# PROC099B_DUT_Reference.net
KiCad netlist of a schematic drawn in Altium Designer
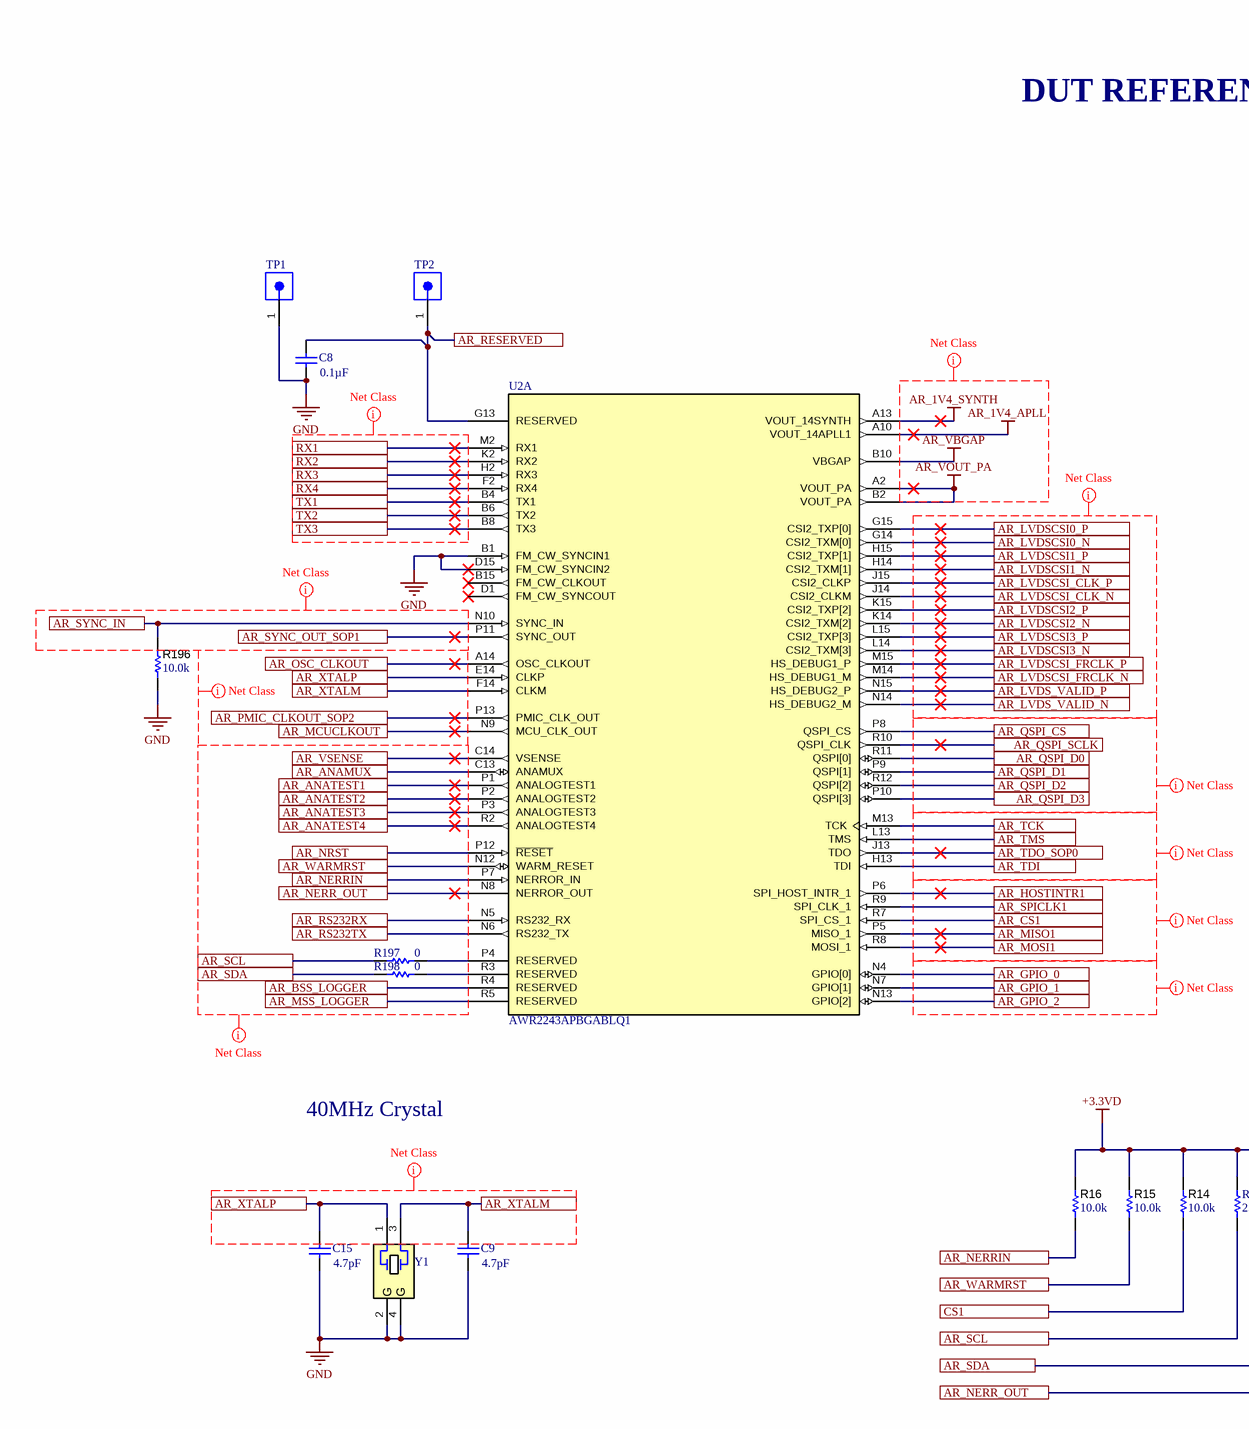
[diagram p0: PROC099B_DUT_Reference.SchDoc, left]
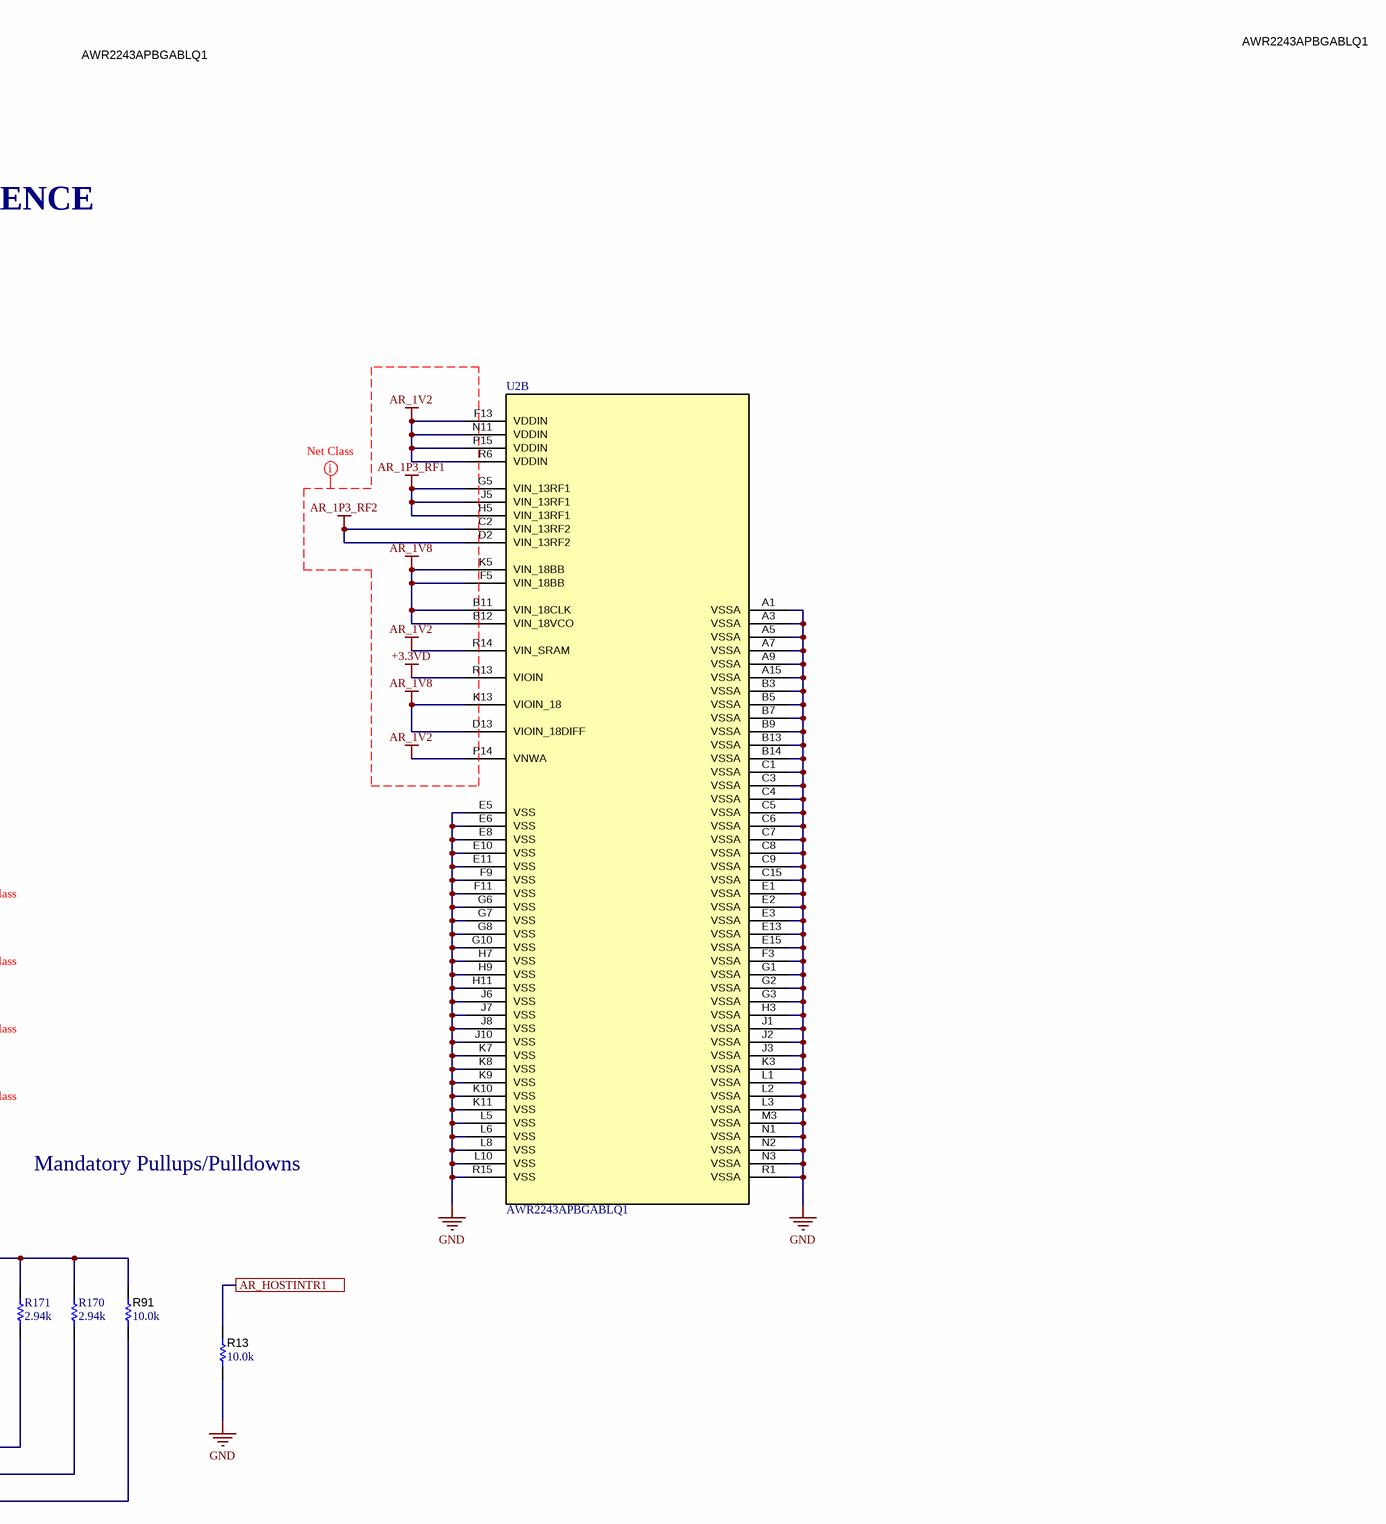
[diagram p1: PROC099B_DUT_Reference.SchDoc, right]

(export (version "E")
  (design (tool "Eeschema 10.0.6"))
  (components
    (comp (ref "C8")
      (value "C0603X7S1A104K030BC")
      (footprint "0201_033")
      (description "CAP, CERM, 0.1 µF, 10 V,+/- 10%, X7S, 0201")
      (fields (field (name "MANUFACTURER") "TDK") (field (name "VALUEDISPLAYED") "0.1µF"))
      (libsource (lib "Altium Vault - TI") (part "Capacitor"))
    )
    (comp (ref "C9")
      (value "GJM1555C1H4R7BB01D")
      (footprint "0402")
      (description "CAP, CERM, 4.7 pF, 50 V, +/- 2%, C0G/NP0, 0402")
      (fields
        (field (name "MANUFACTURER") "MuRata")
        (field (name "VALUEDISPLAYED") "4.7pF")
        (field (name "PUBLISHER") "Texas Instruments")
      )
      (libsource (lib "Altium Vault - TI") (part "CMP-0006367-2"))
    )
    (comp (ref "C15")
      (value "GJM1555C1H4R7BB01D")
      (footprint "0402")
      (description "CAP, CERM, 4.7 pF, 50 V, +/- 2%, C0G/NP0, 0402")
      (fields
        (field (name "MANUFACTURER") "MuRata")
        (field (name "VALUEDISPLAYED") "4.7pF")
        (field (name "PUBLISHER") "Texas Instruments")
      )
      (libsource (lib "Altium Vault - TI") (part "CMP-0006367-2"))
    )
    (comp (ref "R13")
      (value "CRCW040210K0FKED")
      (footprint "0402L")
      (description "RES, 10.0 k, 1%, 0.063 W, AEC-Q200 Grade 0, 0402")
      (fields (field (name "MANUFACTURER") "Vishay-Dale") (field (name "VALUEDISPLAYED") "10.0k"))
      (libsource (lib "Altium Vault - TI") (part "Resistor"))
    )
    (comp (ref "R14")
      (value "CRCW040210K0FKED")
      (footprint "0402L")
      (description "RES, 10.0 k, 1%, 0.063 W, AEC-Q200 Grade 0, 0402")
      (fields (field (name "MANUFACTURER") "Vishay-Dale") (field (name "VALUEDISPLAYED") "10.0k"))
      (libsource (lib "Altium Vault - TI") (part "Resistor"))
    )
    (comp (ref "R15")
      (value "CRCW040210K0FKED")
      (footprint "0402L")
      (description "RES, 10.0 k, 1%, 0.063 W, AEC-Q200 Grade 0, 0402")
      (fields (field (name "MANUFACTURER") "Vishay-Dale") (field (name "VALUEDISPLAYED") "10.0k"))
      (libsource (lib "Altium Vault - TI") (part "Resistor"))
    )
    (comp (ref "R16")
      (value "CRCW040210K0FKED")
      (footprint "0402L")
      (description "RES, 10.0 k, 1%, 0.063 W, AEC-Q200 Grade 0, 0402")
      (fields (field (name "MANUFACTURER") "Vishay-Dale") (field (name "VALUEDISPLAYED") "10.0k"))
      (libsource (lib "Altium Vault - TI") (part "Resistor"))
    )
    (comp (ref "R91")
      (value "CRCW040210K0FKED")
      (footprint "0402L")
      (description "RES, 10.0 k, 1%, 0.063 W, AEC-Q200 Grade 0, 0402")
      (fields (field (name "MANUFACTURER") "Vishay-Dale") (field (name "VALUEDISPLAYED") "10.0k"))
      (libsource (lib "Altium Vault - TI") (part "Resistor"))
    )
    (comp (ref "R170")
      (value "CRCW04022K94FKED")
      (footprint "0402")
      (description "RES, 2.94 k, 1%, 0.063 W, AEC-Q200 Grade 0, 0402")
      (fields (field (name "MANUFACTURER") "Vishay-Dale") (field (name "VALUEDISPLAYED") "2.94k"))
      (libsource (lib "Altium Vault - TI") (part "Resistor"))
    )
    (comp (ref "R171")
      (value "CRCW04022K94FKED")
      (footprint "0402")
      (description "RES, 2.94 k, 1%, 0.063 W, AEC-Q200 Grade 0, 0402")
      (fields (field (name "MANUFACTURER") "Vishay-Dale") (field (name "VALUEDISPLAYED") "2.94k"))
      (libsource (lib "Altium Vault - TI") (part "Resistor"))
    )
    (comp (ref "R196")
      (value "CRCW040210K0FKED")
      (footprint "0402L")
      (description "RES, 10.0 k, 1%, 0.063 W, AEC-Q200 Grade 0, 0402")
      (fields (field (name "MANUFACTURER") "Vishay-Dale") (field (name "VALUEDISPLAYED") "10.0k"))
      (libsource (lib "Altium Vault - TI") (part "CMP-0025958-3"))
    )
    (comp (ref "R197")
      (value "CRCW02010000Z0ED")
      (footprint "0201")
      (description "RES, 0, 5%, 0.05 W, 0201")
      (fields (field (name "MANUFACTURER") "Vishay-Dale") (field (name "VALUEDISPLAYED") "0"))
      (libsource (lib "Altium Vault - TI") (part "Resistor"))
    )
    (comp (ref "R198")
      (value "CRCW02010000Z0ED")
      (footprint "0201")
      (description "RES, 0, 5%, 0.05 W, 0201")
      (fields (field (name "MANUFACTURER") "Vishay-Dale") (field (name "VALUEDISPLAYED") "0"))
      (libsource (lib "Altium Vault - TI") (part "Resistor"))
    )
    (comp (ref "TP1")
      (value "TSW-101-17-T-S")
      (footprint "Samtec_TSW-101-17-T-S")
      (description "Header, 100mil, 1x1, Tin, TH")
      (fields (field (name "MANUFACTURER") "Samtec") (field (name "PUBLISHER") "Texas Instruments"))
      (libsource (lib "Altium Vault - TI") (part "Header_1x1"))
    )
    (comp (ref "TP2")
      (value "TSW-101-17-T-S")
      (footprint "Samtec_TSW-101-17-T-S")
      (description "Header, 100mil, 1x1, Tin, TH")
      (fields (field (name "MANUFACTURER") "Samtec") (field (name "PUBLISHER") "Texas Instruments"))
      (libsource (lib "Altium Vault - TI") (part "Header_1x1"))
    )
    (comp (ref "U2")
      (value "AWR2243APBGABLQ1")
      (footprint "ABL0161A")
      (description "Single Chip 77 and 79 GHz FMCW Transceiver, ABL0161A (FCBGA-161)")
      (fields
        (field (name "MANUFACTURER") "Texas Instruments")
        (field (name "PARTNUMBER") "AWR2243APBGABLQ1")
      )
      (libsource (lib "Altium Vault - TI") (part "CMP-0081285-1"))
    )
    (comp (ref "Y1")
      (value "CX3225SA40000D0PTWCC")
      (footprint "Kyocera_CX3225SA")
      (description "Crystal, 40 MHz, 8pF, SMD")
      (fields (field (name "MANUFACTURER") "Kyocera"))
      (libsource (lib "Altium Vault - TI") (part "XTAL_4P_13_24OPEN"))
    )
  )
  (nets
    (net (code "1") (name "+3.3VD") (class "Default")
      (node (ref "R14") (pin "2") (pinfunction "2_2") (pintype "passive"))
      (node (ref "R15") (pin "2") (pinfunction "2_2") (pintype "passive"))
      (node (ref "R16") (pin "2") (pinfunction "2_2") (pintype "passive"))
      (node (ref "R170") (pin "2") (pinfunction "2_2") (pintype "passive"))
      (node (ref "R171") (pin "2") (pinfunction "2_2") (pintype "passive"))
      (node (ref "R91") (pin "2") (pinfunction "2_2") (pintype "passive"))
      (node (ref "U2") (pin "R13") (pinfunction "VIOIN_R13") (pintype "power_in"))
    )
    (net (code "2") (name "/AR_ANAMUX") (class "Default")
      (node (ref "U2") (pin "C13") (pinfunction "ANAMUX_C13") (pintype "bidirectional"))
    )
    (net (code "3") (name "/AR_ANATEST1") (class "Default")
      (node (ref "U2") (pin "P1") (pinfunction "ANALOGTEST1_P1") (pintype "output"))
    )
    (net (code "4") (name "/AR_ANATEST2") (class "Default")
      (node (ref "U2") (pin "P2") (pinfunction "ANALOGTEST2_P2") (pintype "output"))
    )
    (net (code "5") (name "/AR_ANATEST3") (class "Default")
      (node (ref "U2") (pin "P3") (pinfunction "ANALOGTEST3_P3") (pintype "output"))
    )
    (net (code "6") (name "/AR_ANATEST4") (class "Default")
      (node (ref "U2") (pin "R2") (pinfunction "ANALOGTEST4_R2") (pintype "output"))
    )
    (net (code "7") (name "/AR_BSS_LOGGER") (class "Default")
      (node (ref "U2") (pin "R4") (pinfunction "RESERVED_R4") (pintype "passive"))
    )
    (net (code "8") (name "/AR_CS1") (class "Default")
      (node (ref "U2") (pin "R7") (pinfunction "SPI_CS_1_R7") (pintype "input"))
    )
    (net (code "9") (name "/AR_GPIO_0") (class "Default")
      (node (ref "U2") (pin "N4") (pinfunction "GPIO[0]_N4") (pintype "bidirectional"))
    )
    (net (code "10") (name "/AR_GPIO_1") (class "Default")
      (node (ref "U2") (pin "N7") (pinfunction "GPIO[1]_N7") (pintype "bidirectional"))
    )
    (net (code "11") (name "/AR_GPIO_2") (class "Default")
      (node (ref "U2") (pin "N13") (pinfunction "GPIO[2]_N13") (pintype "bidirectional"))
    )
    (net (code "12") (name "/AR_HOSTINTR1") (class "Default")
      (node (ref "R13") (pin "2") (pinfunction "2_2") (pintype "passive"))
      (node (ref "U2") (pin "P6") (pinfunction "SPI_HOST_INTR_1_P6") (pintype "output"))
    )
    (net (code "13") (name "/AR_LVDSCSI0_N") (class "Default")
      (node (ref "U2") (pin "G14") (pinfunction "CSI2_TXM[0]_G14") (pintype "output"))
    )
    (net (code "14") (name "/AR_LVDSCSI0_P") (class "Default")
      (node (ref "U2") (pin "G15") (pinfunction "CSI2_TXP[0]_G15") (pintype "output"))
    )
    (net (code "15") (name "/AR_LVDSCSI1_N") (class "Default")
      (node (ref "U2") (pin "H14") (pinfunction "CSI2_TXM[1]_H14") (pintype "output"))
    )
    (net (code "16") (name "/AR_LVDSCSI1_P") (class "Default")
      (node (ref "U2") (pin "H15") (pinfunction "CSI2_TXP[1]_H15") (pintype "output"))
    )
    (net (code "17") (name "/AR_LVDSCSI2_N") (class "Default")
      (node (ref "U2") (pin "K14") (pinfunction "CSI2_TXM[2]_K14") (pintype "output"))
    )
    (net (code "18") (name "/AR_LVDSCSI2_P") (class "Default")
      (node (ref "U2") (pin "K15") (pinfunction "CSI2_TXP[2]_K15") (pintype "output"))
    )
    (net (code "19") (name "/AR_LVDSCSI3_N") (class "Default")
      (node (ref "U2") (pin "L14") (pinfunction "CSI2_TXM[3]_L14") (pintype "output"))
    )
    (net (code "20") (name "/AR_LVDSCSI3_P") (class "Default")
      (node (ref "U2") (pin "L15") (pinfunction "CSI2_TXP[3]_L15") (pintype "output"))
    )
    (net (code "21") (name "/AR_LVDSCSI_CLK_N") (class "Default")
      (node (ref "U2") (pin "J14") (pinfunction "CSI2_CLKM_J14") (pintype "output"))
    )
    (net (code "22") (name "/AR_LVDSCSI_CLK_P") (class "Default")
      (node (ref "U2") (pin "J15") (pinfunction "CSI2_CLKP_J15") (pintype "output"))
    )
    (net (code "23") (name "/AR_LVDSCSI_FRCLK_N") (class "Default")
      (node (ref "U2") (pin "M14") (pinfunction "HS_DEBUG1_M_M14") (pintype "output"))
    )
    (net (code "24") (name "/AR_LVDSCSI_FRCLK_P") (class "Default")
      (node (ref "U2") (pin "M15") (pinfunction "HS_DEBUG1_P_M15") (pintype "output"))
    )
    (net (code "25") (name "/AR_LVDS_VALID_N") (class "Default")
      (node (ref "U2") (pin "N14") (pinfunction "HS_DEBUG2_M_N14") (pintype "output"))
    )
    (net (code "26") (name "/AR_LVDS_VALID_P") (class "Default")
      (node (ref "U2") (pin "N15") (pinfunction "HS_DEBUG2_P_N15") (pintype "output"))
    )
    (net (code "27") (name "/AR_MCUCLKOUT") (class "Default")
      (node (ref "U2") (pin "N9") (pinfunction "MCU_CLK_OUT_N9") (pintype "output"))
    )
    (net (code "28") (name "/AR_MISO1") (class "Default")
      (node (ref "U2") (pin "P5") (pinfunction "MISO_1_P5") (pintype "output"))
    )
    (net (code "29") (name "/AR_MOSI1") (class "Default")
      (node (ref "U2") (pin "R8") (pinfunction "MOSI_1_R8") (pintype "input"))
    )
    (net (code "30") (name "/AR_MSS_LOGGER") (class "Default")
      (node (ref "U2") (pin "R5") (pinfunction "RESERVED_R5") (pintype "passive"))
    )
    (net (code "31") (name "/AR_NERRIN") (class "Default")
      (node (ref "R16") (pin "1") (pinfunction "1_1") (pintype "passive"))
      (node (ref "U2") (pin "P7") (pinfunction "NERROR_IN_P7") (pintype "input"))
    )
    (net (code "32") (name "/AR_NERR_OUT") (class "Default")
      (node (ref "R91") (pin "1") (pinfunction "1_1") (pintype "passive"))
      (node (ref "U2") (pin "N8") (pinfunction "NERROR_OUT_N8") (pintype "open_collector"))
    )
    (net (code "33") (name "/AR_NRST") (class "Default")
      (node (ref "U2") (pin "P12") (pinfunction "RESET_P12") (pintype "input"))
    )
    (net (code "34") (name "/AR_OSC_CLKOUT") (class "Default")
      (node (ref "U2") (pin "A14") (pinfunction "OSC_CLKOUT_A14") (pintype "output"))
    )
    (net (code "35") (name "/AR_PMIC_CLKOUT_SOP2") (class "Default")
      (node (ref "U2") (pin "P13") (pinfunction "PMIC_CLK_OUT_P13") (pintype "output"))
    )
    (net (code "36") (name "/AR_QSPI_CS") (class "Default")
      (node (ref "U2") (pin "P8") (pinfunction "QSPI_CS_P8") (pintype "output"))
    )
    (net (code "37") (name "/AR_QSPI_D0") (class "Default")
      (node (ref "U2") (pin "R11") (pinfunction "QSPI[0]_R11") (pintype "bidirectional"))
    )
    (net (code "38") (name "/AR_QSPI_D1") (class "Default")
      (node (ref "U2") (pin "P9") (pinfunction "QSPI[1]_P9") (pintype "bidirectional"))
    )
    (net (code "39") (name "/AR_QSPI_D2") (class "Default")
      (node (ref "U2") (pin "R12") (pinfunction "QSPI[2]_R12") (pintype "bidirectional"))
    )
    (net (code "40") (name "/AR_QSPI_D3") (class "Default")
      (node (ref "U2") (pin "P10") (pinfunction "QSPI[3]_P10") (pintype "bidirectional"))
    )
    (net (code "41") (name "/AR_QSPI_SCLK") (class "Default")
      (node (ref "U2") (pin "R10") (pinfunction "QSPI_CLK_R10") (pintype "output"))
    )
    (net (code "42") (name "/AR_RESERVED") (class "Default")
      (node (ref "C8") (pin "1") (pinfunction "1_1") (pintype "passive"))
      (node (ref "TP2") (pin "1") (pinfunction "1_1") (pintype "passive"))
      (node (ref "U2") (pin "G13") (pinfunction "RESERVED_G13") (pintype "power_in"))
    )
    (net (code "43") (name "/AR_RS232RX") (class "Default")
      (node (ref "U2") (pin "N5") (pinfunction "RS232_RX_N5") (pintype "input"))
    )
    (net (code "44") (name "/AR_RS232TX") (class "Default")
      (node (ref "U2") (pin "N6") (pinfunction "RS232_TX_N6") (pintype "output"))
    )
    (net (code "45") (name "/AR_SCL") (class "Default")
      (node (ref "R171") (pin "1") (pinfunction "1_1") (pintype "passive"))
      (node (ref "R197") (pin "1") (pinfunction "1_1") (pintype "passive"))
    )
    (net (code "46") (name "/AR_SDA") (class "Default")
      (node (ref "R170") (pin "1") (pinfunction "1_1") (pintype "passive"))
      (node (ref "R198") (pin "1") (pinfunction "1_1") (pintype "passive"))
    )
    (net (code "47") (name "/AR_SPICLK1") (class "Default")
      (node (ref "U2") (pin "R9") (pinfunction "SPI_CLK_1_R9") (pintype "input"))
    )
    (net (code "48") (name "/AR_SYNC_IN") (class "Default")
      (node (ref "R196") (pin "2") (pinfunction "2_2") (pintype "passive"))
      (node (ref "U2") (pin "N10") (pinfunction "SYNC_IN_N10") (pintype "input"))
    )
    (net (code "49") (name "/AR_SYNC_OUT_SOP1") (class "Default")
      (node (ref "U2") (pin "P11") (pinfunction "SYNC_OUT_P11") (pintype "output"))
    )
    (net (code "50") (name "/AR_TCK") (class "Default")
      (node (ref "U2") (pin "M13") (pinfunction "TCK_M13") (pintype "input"))
    )
    (net (code "51") (name "/AR_TDI") (class "Default")
      (node (ref "U2") (pin "H13") (pinfunction "TDI_H13") (pintype "input"))
    )
    (net (code "52") (name "/AR_TDO_SOP0") (class "Default")
      (node (ref "U2") (pin "J13") (pinfunction "TDO_J13") (pintype "output"))
    )
    (net (code "53") (name "/AR_TMS") (class "Default")
      (node (ref "U2") (pin "L13") (pinfunction "TMS_L13") (pintype "input"))
    )
    (net (code "54") (name "/AR_VSENSE") (class "Default")
      (node (ref "U2") (pin "C14") (pinfunction "VSENSE_C14") (pintype "output"))
    )
    (net (code "55") (name "/AR_WARMRST") (class "Default")
      (node (ref "R15") (pin "1") (pinfunction "1_1") (pintype "passive"))
      (node (ref "U2") (pin "N12") (pinfunction "WARM_RESET_N12") (pintype "bidirectional"))
    )
    (net (code "56") (name "/AR_XTALM") (class "Default")
      (node (ref "C9") (pin "1") (pinfunction "1_1") (pintype "passive"))
      (node (ref "U2") (pin "F14") (pinfunction "CLKM_F14") (pintype "input"))
      (node (ref "Y1") (pin "3") (pinfunction "3_3") (pintype "passive"))
    )
    (net (code "57") (name "/AR_XTALP") (class "Default")
      (node (ref "C15") (pin "2") (pinfunction "2_2") (pintype "passive"))
      (node (ref "U2") (pin "E14") (pinfunction "CLKP_E14") (pintype "input"))
      (node (ref "Y1") (pin "1") (pinfunction "1_1") (pintype "passive"))
    )
    (net (code "58") (name "/CS1") (class "Default")
      (node (ref "R14") (pin "1") (pinfunction "1_1") (pintype "passive"))
    )
    (net (code "59") (name "/RX1") (class "Default")
      (node (ref "U2") (pin "M2") (pinfunction "RX1_M2") (pintype "input"))
    )
    (net (code "60") (name "/RX2") (class "Default")
      (node (ref "U2") (pin "K2") (pinfunction "RX2_K2") (pintype "input"))
    )
    (net (code "61") (name "/RX3") (class "Default")
      (node (ref "U2") (pin "H2") (pinfunction "RX3_H2") (pintype "input"))
    )
    (net (code "62") (name "/RX4") (class "Default")
      (node (ref "U2") (pin "F2") (pinfunction "RX4_F2") (pintype "input"))
    )
    (net (code "63") (name "/TX1") (class "Default")
      (node (ref "U2") (pin "B4") (pinfunction "TX1_B4") (pintype "output"))
    )
    (net (code "64") (name "/TX2") (class "Default")
      (node (ref "U2") (pin "B6") (pinfunction "TX2_B6") (pintype "output"))
    )
    (net (code "65") (name "/TX3") (class "Default")
      (node (ref "U2") (pin "B8") (pinfunction "TX3_B8") (pintype "output"))
    )
    (net (code "66") (name "AR_1P3_RF1") (class "Default")
      (node (ref "U2") (pin "G5") (pinfunction "VIN_13RF1_G5") (pintype "power_in"))
      (node (ref "U2") (pin "H5") (pinfunction "VIN_13RF1_H5") (pintype "power_in"))
      (node (ref "U2") (pin "J5") (pinfunction "VIN_13RF1_J5") (pintype "power_in"))
    )
    (net (code "67") (name "AR_1P3_RF2") (class "Default")
      (node (ref "U2") (pin "C2") (pinfunction "VIN_13RF2_C2") (pintype "power_in"))
      (node (ref "U2") (pin "D2") (pinfunction "VIN_13RF2_D2") (pintype "power_in"))
    )
    (net (code "68") (name "AR_1V2") (class "Default")
      (node (ref "U2") (pin "F13") (pinfunction "VDDIN_F13") (pintype "power_in"))
      (node (ref "U2") (pin "N11") (pinfunction "VDDIN_N11") (pintype "power_in"))
      (node (ref "U2") (pin "P14") (pinfunction "VNWA_P14") (pintype "power_in"))
      (node (ref "U2") (pin "P15") (pinfunction "VDDIN_P15") (pintype "power_in"))
      (node (ref "U2") (pin "R14") (pinfunction "VIN_SRAM_R14") (pintype "power_in"))
      (node (ref "U2") (pin "R6") (pinfunction "VDDIN_R6") (pintype "power_in"))
    )
    (net (code "69") (name "AR_1V4_APLL") (class "Default")
      (node (ref "U2") (pin "A10") (pinfunction "VOUT_14APLL1_A10") (pintype "output"))
    )
    (net (code "70") (name "AR_1V4_SYNTH") (class "Default")
      (node (ref "U2") (pin "A13") (pinfunction "VOUT_14SYNTH_A13") (pintype "output"))
    )
    (net (code "71") (name "AR_1V8") (class "Default")
      (node (ref "U2") (pin "B11") (pinfunction "VIN_18CLK_B11") (pintype "power_in"))
      (node (ref "U2") (pin "B12") (pinfunction "VIN_18VCO_B12") (pintype "power_in"))
      (node (ref "U2") (pin "D13") (pinfunction "VIOIN_18DIFF_D13") (pintype "power_in"))
      (node (ref "U2") (pin "F5") (pinfunction "VIN_18BB_F5") (pintype "power_in"))
      (node (ref "U2") (pin "K13") (pinfunction "VIOIN_18_K13") (pintype "power_in"))
      (node (ref "U2") (pin "K5") (pinfunction "VIN_18BB_K5") (pintype "power_in"))
    )
    (net (code "72") (name "AR_VBGAP") (class "Default")
      (node (ref "U2") (pin "B10") (pinfunction "VBGAP_B10") (pintype "output"))
    )
    (net (code "73") (name "AR_VOUT_PA") (class "Default")
      (node (ref "U2") (pin "A2") (pinfunction "VOUT_PA_A2") (pintype "output"))
      (node (ref "U2") (pin "B2") (pinfunction "VOUT_PA_B2") (pintype "output"))
    )
    (net (code "74") (name "GND") (class "Default")
      (node (ref "C15") (pin "1") (pinfunction "1_1") (pintype "passive"))
      (node (ref "C8") (pin "2") (pinfunction "2_2") (pintype "passive"))
      (node (ref "C9") (pin "2") (pinfunction "2_2") (pintype "passive"))
      (node (ref "R13") (pin "1") (pinfunction "1_1") (pintype "passive"))
      (node (ref "R196") (pin "1") (pinfunction "1_1") (pintype "passive"))
      (node (ref "TP1") (pin "1") (pinfunction "1_1") (pintype "passive"))
      (node (ref "U2") (pin "A1") (pinfunction "VSSA_A1") (pintype "power_in"))
      (node (ref "U2") (pin "A15") (pinfunction "VSSA_A15") (pintype "power_in"))
      (node (ref "U2") (pin "A3") (pinfunction "VSSA_A3") (pintype "power_in"))
      (node (ref "U2") (pin "A5") (pinfunction "VSSA_A5") (pintype "power_in"))
      (node (ref "U2") (pin "A7") (pinfunction "VSSA_A7") (pintype "power_in"))
      (node (ref "U2") (pin "A9") (pinfunction "VSSA_A9") (pintype "power_in"))
      (node (ref "U2") (pin "B1") (pinfunction "FM_CW_SYNCIN1_B1") (pintype "input"))
      (node (ref "U2") (pin "B13") (pinfunction "VSSA_B13") (pintype "power_in"))
      (node (ref "U2") (pin "B14") (pinfunction "VSSA_B14") (pintype "power_in"))
      (node (ref "U2") (pin "B3") (pinfunction "VSSA_B3") (pintype "power_in"))
      (node (ref "U2") (pin "B5") (pinfunction "VSSA_B5") (pintype "power_in"))
      (node (ref "U2") (pin "B7") (pinfunction "VSSA_B7") (pintype "power_in"))
      (node (ref "U2") (pin "B9") (pinfunction "VSSA_B9") (pintype "power_in"))
      (node (ref "U2") (pin "C1") (pinfunction "VSSA_C1") (pintype "power_in"))
      (node (ref "U2") (pin "C15") (pinfunction "VSSA_C15") (pintype "power_in"))
      (node (ref "U2") (pin "C3") (pinfunction "VSSA_C3") (pintype "power_in"))
      (node (ref "U2") (pin "C4") (pinfunction "VSSA_C4") (pintype "power_in"))
      (node (ref "U2") (pin "C5") (pinfunction "VSSA_C5") (pintype "power_in"))
      (node (ref "U2") (pin "C6") (pinfunction "VSSA_C6") (pintype "power_in"))
      (node (ref "U2") (pin "C7") (pinfunction "VSSA_C7") (pintype "power_in"))
      (node (ref "U2") (pin "C8") (pinfunction "VSSA_C8") (pintype "power_in"))
      (node (ref "U2") (pin "C9") (pinfunction "VSSA_C9") (pintype "power_in"))
      (node (ref "U2") (pin "D15") (pinfunction "FM_CW_SYNCIN2_D15") (pintype "input"))
      (node (ref "U2") (pin "E1") (pinfunction "VSSA_E1") (pintype "power_in"))
      (node (ref "U2") (pin "E10") (pinfunction "VSS_E10") (pintype "power_in"))
      (node (ref "U2") (pin "E11") (pinfunction "VSS_E11") (pintype "power_in"))
      (node (ref "U2") (pin "E13") (pinfunction "VSSA_E13") (pintype "power_in"))
      (node (ref "U2") (pin "E15") (pinfunction "VSSA_E15") (pintype "power_in"))
      (node (ref "U2") (pin "E2") (pinfunction "VSSA_E2") (pintype "power_in"))
      (node (ref "U2") (pin "E3") (pinfunction "VSSA_E3") (pintype "power_in"))
      (node (ref "U2") (pin "E5") (pinfunction "VSS_E5") (pintype "power_in"))
      (node (ref "U2") (pin "E6") (pinfunction "VSS_E6") (pintype "power_in"))
      (node (ref "U2") (pin "E8") (pinfunction "VSS_E8") (pintype "power_in"))
      (node (ref "U2") (pin "F11") (pinfunction "VSS_F11") (pintype "power_in"))
      (node (ref "U2") (pin "F3") (pinfunction "VSSA_F3") (pintype "power_in"))
      (node (ref "U2") (pin "F9") (pinfunction "VSS_F9") (pintype "power_in"))
      (node (ref "U2") (pin "G1") (pinfunction "VSSA_G1") (pintype "power_in"))
      (node (ref "U2") (pin "G10") (pinfunction "VSS_G10") (pintype "power_in"))
      (node (ref "U2") (pin "G2") (pinfunction "VSSA_G2") (pintype "power_in"))
      (node (ref "U2") (pin "G3") (pinfunction "VSSA_G3") (pintype "power_in"))
      (node (ref "U2") (pin "G6") (pinfunction "VSS_G6") (pintype "power_in"))
      (node (ref "U2") (pin "G7") (pinfunction "VSS_G7") (pintype "power_in"))
      (node (ref "U2") (pin "G8") (pinfunction "VSS_G8") (pintype "power_in"))
      (node (ref "U2") (pin "H11") (pinfunction "VSS_H11") (pintype "power_in"))
      (node (ref "U2") (pin "H3") (pinfunction "VSSA_H3") (pintype "power_in"))
      (node (ref "U2") (pin "H7") (pinfunction "VSS_H7") (pintype "power_in"))
      (node (ref "U2") (pin "H9") (pinfunction "VSS_H9") (pintype "power_in"))
      (node (ref "U2") (pin "J1") (pinfunction "VSSA_J1") (pintype "power_in"))
      (node (ref "U2") (pin "J10") (pinfunction "VSS_J10") (pintype "power_in"))
      (node (ref "U2") (pin "J2") (pinfunction "VSSA_J2") (pintype "power_in"))
      (node (ref "U2") (pin "J3") (pinfunction "VSSA_J3") (pintype "power_in"))
      (node (ref "U2") (pin "J6") (pinfunction "VSS_J6") (pintype "power_in"))
      (node (ref "U2") (pin "J7") (pinfunction "VSS_J7") (pintype "power_in"))
      (node (ref "U2") (pin "J8") (pinfunction "VSS_J8") (pintype "power_in"))
      (node (ref "U2") (pin "K10") (pinfunction "VSS_K10") (pintype "power_in"))
      (node (ref "U2") (pin "K11") (pinfunction "VSS_K11") (pintype "power_in"))
      (node (ref "U2") (pin "K3") (pinfunction "VSSA_K3") (pintype "power_in"))
      (node (ref "U2") (pin "K7") (pinfunction "VSS_K7") (pintype "power_in"))
      (node (ref "U2") (pin "K8") (pinfunction "VSS_K8") (pintype "power_in"))
      (node (ref "U2") (pin "K9") (pinfunction "VSS_K9") (pintype "power_in"))
      (node (ref "U2") (pin "L1") (pinfunction "VSSA_L1") (pintype "power_in"))
      (node (ref "U2") (pin "L10") (pinfunction "VSS_L10") (pintype "power_in"))
      (node (ref "U2") (pin "L2") (pinfunction "VSSA_L2") (pintype "power_in"))
      (node (ref "U2") (pin "L3") (pinfunction "VSSA_L3") (pintype "power_in"))
      (node (ref "U2") (pin "L5") (pinfunction "VSS_L5") (pintype "power_in"))
      (node (ref "U2") (pin "L6") (pinfunction "VSS_L6") (pintype "power_in"))
      (node (ref "U2") (pin "L8") (pinfunction "VSS_L8") (pintype "power_in"))
      (node (ref "U2") (pin "M3") (pinfunction "VSSA_M3") (pintype "power_in"))
      (node (ref "U2") (pin "N1") (pinfunction "VSSA_N1") (pintype "power_in"))
      (node (ref "U2") (pin "N2") (pinfunction "VSSA_N2") (pintype "power_in"))
      (node (ref "U2") (pin "N3") (pinfunction "VSSA_N3") (pintype "power_in"))
      (node (ref "U2") (pin "R1") (pinfunction "VSSA_R1") (pintype "power_in"))
      (node (ref "U2") (pin "R15") (pinfunction "VSS_R15") (pintype "power_in"))
      (node (ref "Y1") (pin "2") (pinfunction "GND_2") (pintype "power_in"))
      (node (ref "Y1") (pin "4") (pinfunction "GND_4") (pintype "power_in"))
    )
    (net (code "75") (name "Net-(R197-Pad2)") (class "Default")
      (node (ref "R197") (pin "2") (pinfunction "2_2") (pintype "passive"))
      (node (ref "U2") (pin "P4") (pinfunction "RESERVED_P4") (pintype "passive"))
    )
    (net (code "76") (name "Net-(R198-Pad2)") (class "Default")
      (node (ref "R198") (pin "2") (pinfunction "2_2") (pintype "passive"))
      (node (ref "U2") (pin "R3") (pinfunction "RESERVED_R3") (pintype "passive"))
    )
    (net (code "77") (name "unconnected-(U2A-FM_CW_CLKOUT-PadB15)") (class "Default")
      (node (ref "U2") (pin "B15") (pinfunction "FM_CW_CLKOUT_B15") (pintype "output+no_connect"))
    )
    (net (code "78") (name "unconnected-(U2A-FM_CW_SYNCOUT-PadD1)") (class "Default")
      (node (ref "U2") (pin "D1") (pinfunction "FM_CW_SYNCOUT_D1") (pintype "output+no_connect"))
    )
  )
)
